# OLM-periph-probe_ambient.net
KiCad netlist of a schematic drawn in EAGLE
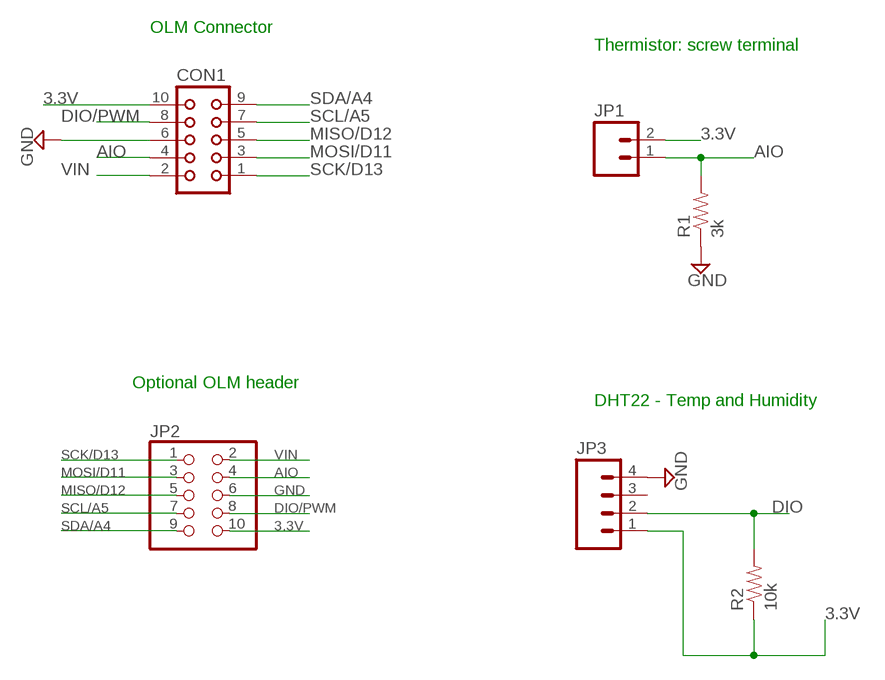
[diagram p0: schematic, sheet 1]

(export (version "E")
  (design (tool "Eeschema 10.0.6"))
  (components
    (comp (ref "CON1")
      (value "CON10L")
      (footprint "eagle-import:CON10L")
      (libsource (lib "eagle-import") (part "CON10L"))
    )
    (comp (ref "JP1")
      (value "M025MM")
      (footprint "eagle-import:SCREWTERMINAL-5MM-2")
      (libsource (lib "eagle-import") (part "M025MM"))
    )
    (comp (ref "JP2")
      (value "PINHD-2X5")
      (footprint "eagle-import:2X05")
      (libsource (lib "eagle-import") (part "PINHD-2X5"))
    )
    (comp (ref "JP3")
      (value "M04LOCK")
      (footprint "eagle-import:1X04_LOCK")
      (libsource (lib "eagle-import") (part "M04LOCK"))
    )
    (comp (ref "R1")
      (value "3k")
      (footprint "eagle-import:AXIAL-0.4")
      (libsource (lib "eagle-import") (part "RESISTORPTH-1/4W"))
    )
    (comp (ref "R2")
      (value "10k")
      (footprint "eagle-import:AXIAL-0.4")
      (libsource (lib "eagle-import") (part "RESISTORPTH-1/4W"))
    )
  )
  (nets
    (net (code "1") (name "/3.3V") (class "Default")
      (node (ref "CON1") (pin "10") (pinfunction "10_10") (pintype "passive"))
      (node (ref "JP1") (pin "2") (pinfunction "2_2") (pintype "passive"))
      (node (ref "JP2") (pin "10") (pinfunction "10_10") (pintype "passive"))
      (node (ref "JP3") (pin "1") (pinfunction "1_1") (pintype "passive"))
      (node (ref "R2") (pin "P$1") (pinfunction "1_P$1") (pintype "passive"))
    )
    (net (code "2") (name "/AIO") (class "Default")
      (node (ref "CON1") (pin "4") (pinfunction "4_4") (pintype "passive"))
      (node (ref "JP1") (pin "1") (pinfunction "1_1") (pintype "passive"))
      (node (ref "JP2") (pin "4") (pinfunction "4_4") (pintype "passive"))
      (node (ref "R1") (pin "P$2") (pinfunction "2_P$2") (pintype "passive"))
    )
    (net (code "3") (name "/DIO") (class "Default")
      (node (ref "JP3") (pin "2") (pinfunction "2_2") (pintype "passive"))
      (node (ref "R2") (pin "P$2") (pinfunction "2_P$2") (pintype "passive"))
    )
    (net (code "4") (name "/DIO{slash}PWM") (class "Default")
      (node (ref "CON1") (pin "8") (pinfunction "8_8") (pintype "passive"))
      (node (ref "JP2") (pin "8") (pinfunction "8_8") (pintype "passive"))
    )
    (net (code "5") (name "/MISO{slash}D12") (class "Default")
      (node (ref "CON1") (pin "5") (pinfunction "5_5") (pintype "passive"))
      (node (ref "JP2") (pin "5") (pinfunction "5_5") (pintype "passive"))
    )
    (net (code "6") (name "/MOSI{slash}D11") (class "Default")
      (node (ref "CON1") (pin "3") (pinfunction "3_3") (pintype "passive"))
      (node (ref "JP2") (pin "3") (pinfunction "3_3") (pintype "passive"))
    )
    (net (code "7") (name "/SCK{slash}D13") (class "Default")
      (node (ref "CON1") (pin "1") (pinfunction "1_1") (pintype "passive"))
      (node (ref "JP2") (pin "1") (pinfunction "1_1") (pintype "passive"))
    )
    (net (code "8") (name "/SCL{slash}A5") (class "Default")
      (node (ref "CON1") (pin "7") (pinfunction "7_7") (pintype "passive"))
      (node (ref "JP2") (pin "7") (pinfunction "7_7") (pintype "passive"))
    )
    (net (code "9") (name "/SDA{slash}A4") (class "Default")
      (node (ref "CON1") (pin "9") (pinfunction "9_9") (pintype "passive"))
      (node (ref "JP2") (pin "9") (pinfunction "9_9") (pintype "passive"))
    )
    (net (code "10") (name "/VIN") (class "Default")
      (node (ref "CON1") (pin "2") (pinfunction "2_2") (pintype "passive"))
      (node (ref "JP2") (pin "2") (pinfunction "2_2") (pintype "passive"))
    )
    (net (code "11") (name "GND") (class "Default")
      (node (ref "CON1") (pin "6") (pinfunction "6_6") (pintype "passive"))
      (node (ref "JP2") (pin "6") (pinfunction "6_6") (pintype "passive"))
      (node (ref "JP3") (pin "4") (pinfunction "4_4") (pintype "passive"))
      (node (ref "R1") (pin "P$1") (pinfunction "1_P$1") (pintype "passive"))
    )
    (net (code "12") (name "unconnected-(JP3-Pad3)") (class "Default")
      (node (ref "JP3") (pin "3") (pinfunction "3_3") (pintype "passive"))
    )
  )
)
